# relay.net
KiCad netlist of a schematic drawn in Altium Designer
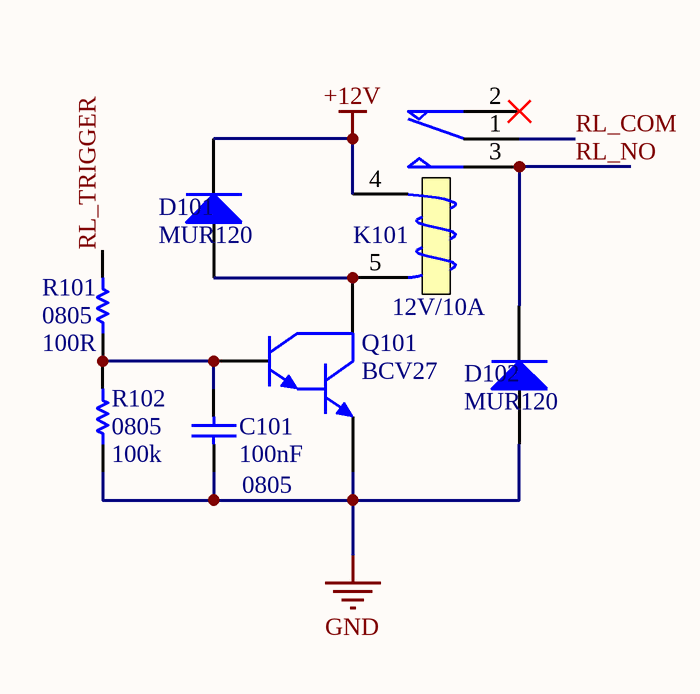
[diagram p0: relay.SchDoc]

(export (version "E")
  (design (tool "Eeschema 10.0.6"))
  (components
    (comp (ref "C101")
      (value "100nF")
      (footprint "0805")
      (description "Capacitor")
      (fields (field (name "VOLTAGE") "25V"))
      (libsource (lib "Miscellaneous Devices") (part "Cap"))
    )
    (comp (ref "D101")
      (value "MUR120")
      (footprint "DIO10.2-7x2.7")
      (description "Default Diode")
      (libsource (lib "Miscellaneous Devices") (part "Diode"))
    )
    (comp (ref "D102")
      (value "MUR120")
      (footprint "DSO-C2/X2.3")
      (description "Default Diode")
      (libsource (lib "Miscellaneous Devices") (part "Diode"))
    )
    (comp (ref "K101")
      (value "12V/10A")
      (footprint "RELE")
      (description "SPDT Relay")
      (libsource (lib "Miscellaneous Devices") (part "Relay"))
    )
    (comp (ref "Q101")
      (value "BCV27")
      (footprint "SOT95P240-3N")
      (description "NPN Darlington Bipolar Transistor")
      (libsource (lib "Miscellaneous Devices") (part "NPN1"))
    )
    (comp (ref "R101")
      (value "0805")
      (footprint "0805C")
      (description "Resistor")
      (fields (field (name "ALTIUM_VALUE") "100R"))
      (libsource (lib "Miscellaneous Devices") (part "Res1"))
    )
    (comp (ref "R102")
      (value "0805")
      (footprint "0805C")
      (description "Resistor")
      (fields (field (name "ALTIUM_VALUE") "100k"))
      (libsource (lib "Miscellaneous Devices") (part "Res1"))
    )
  )
  (nets
    (net (code "1") (name "+12V") (class "Default")
      (node (ref "D101") (pin "2") (pinfunction "K_2") (pintype "passive"))
      (node (ref "K101") (pin "4") (pinfunction "T1_4") (pintype "passive"))
    )
    (net (code "2") (name "/RL_COM") (class "Default")
      (node (ref "K101") (pin "1") (pinfunction "COM_1") (pintype "passive"))
    )
    (net (code "3") (name "/RL_NO") (class "Default")
      (node (ref "D102") (pin "2") (pinfunction "K_2") (pintype "passive"))
      (node (ref "K101") (pin "3") (pinfunction "NO_3") (pintype "passive"))
    )
    (net (code "4") (name "/RL_TRIGGER") (class "Default")
      (node (ref "R101") (pin "2") (pinfunction "2_2") (pintype "passive"))
    )
    (net (code "5") (name "GND") (class "Default")
      (node (ref "C101") (pin "1") (pinfunction "1_1") (pintype "passive"))
      (node (ref "D102") (pin "1") (pinfunction "A_1") (pintype "passive"))
      (node (ref "Q101") (pin "3") (pinfunction "E_3") (pintype "passive"))
      (node (ref "R102") (pin "1") (pinfunction "1_1") (pintype "passive"))
    )
    (net (code "6") (name "Net-(D101-A)") (class "Default")
      (node (ref "D101") (pin "1") (pinfunction "A_1") (pintype "passive"))
      (node (ref "K101") (pin "5") (pinfunction "T2_5") (pintype "passive"))
      (node (ref "Q101") (pin "1") (pinfunction "C_1") (pintype "passive"))
    )
    (net (code "7") (name "Net-(Q101-B)") (class "Default")
      (node (ref "C101") (pin "2") (pinfunction "2_2") (pintype "passive"))
      (node (ref "Q101") (pin "2") (pinfunction "B_2") (pintype "passive"))
      (node (ref "R101") (pin "1") (pinfunction "1_1") (pintype "passive"))
      (node (ref "R102") (pin "2") (pinfunction "2_2") (pintype "passive"))
    )
    (net (code "8") (name "unconnected-(K101-NC-Pad2)") (class "Default")
      (node (ref "K101") (pin "2") (pinfunction "NC_2") (pintype "passive+no_connect"))
    )
  )
)
